# CW308_Power.net
KiCad netlist of a schematic drawn in Altium Designer
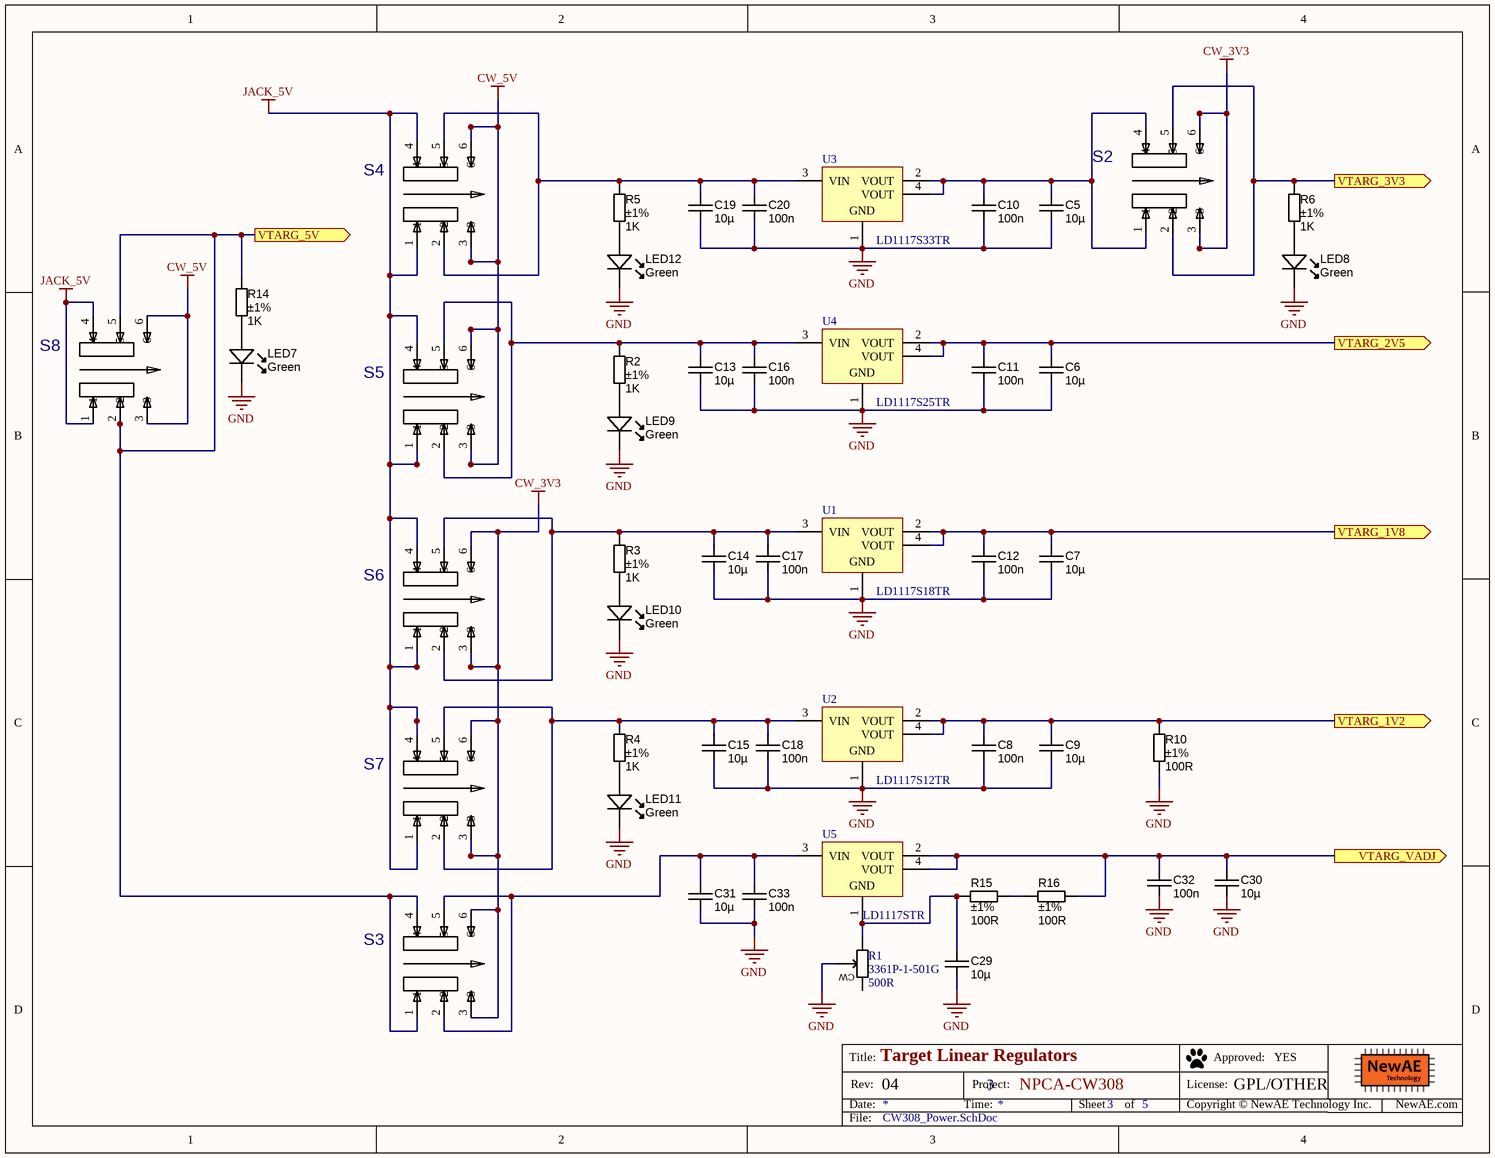
[diagram p0: CW308_Power.SchDoc]

(export (version "E")
  (design (tool "Eeschema 10.0.6"))
  (components
    (comp (ref "C5")
      (value "10µ")
      (footprint "CAPC2012X135N")
      (description "Capacitor SMD Cer 10uF 10% 10V X5R 0805")
      (fields (field (name "TOLERANCE") "±10%") (field (name "Comment") "approved sub OK"))
      (libsource (lib "PBL - Capacitors") (part "CAPC_10u_0805_10V"))
    )
    (comp (ref "C6")
      (value "10µ")
      (footprint "CAPC2012X135N")
      (description "Capacitor SMD Cer 10uF 10% 10V X5R 0805")
      (fields (field (name "TOLERANCE") "±10%") (field (name "Comment") "approved sub OK"))
      (libsource (lib "PBL - Capacitors") (part "CAPC_10u_0805_10V"))
    )
    (comp (ref "C7")
      (value "10µ")
      (footprint "CAPC2012X135N")
      (description "Capacitor SMD Cer 10uF 10% 10V X5R 0805")
      (fields (field (name "TOLERANCE") "±10%") (field (name "Comment") "approved sub OK"))
      (libsource (lib "PBL - Capacitors") (part "CAPC_10u_0805_10V"))
    )
    (comp (ref "C8")
      (value "100n")
      (footprint "CAPC1608X90N")
      (description "Capacitor SMD Cer 100nF 10% 50V X7R 0603")
      (fields (field (name "TOLERANCE") "±10%") (field (name "Comment") "approved sub OK"))
      (libsource (lib "PBL - Capacitors") (part "CAPC_100n_0603_X7R_50V_10%"))
    )
    (comp (ref "C9")
      (value "10µ")
      (footprint "CAPC2012X135N")
      (description "Capacitor SMD Cer 10uF 10% 10V X5R 0805")
      (fields (field (name "TOLERANCE") "±10%") (field (name "Comment") "approved sub OK"))
      (libsource (lib "PBL - Capacitors") (part "CAPC_10u_0805_10V"))
    )
    (comp (ref "C10")
      (value "100n")
      (footprint "CAPC1608X90N")
      (description "Capacitor SMD Cer 100nF 10% 50V X7R 0603")
      (fields (field (name "TOLERANCE") "±10%") (field (name "Comment") "approved sub OK"))
      (libsource (lib "PBL - Capacitors") (part "CAPC_100n_0603_X7R_50V_10%"))
    )
    (comp (ref "C11")
      (value "100n")
      (footprint "CAPC1608X90N")
      (description "Capacitor SMD Cer 100nF 10% 50V X7R 0603")
      (fields (field (name "TOLERANCE") "±10%") (field (name "Comment") "approved sub OK"))
      (libsource (lib "PBL - Capacitors") (part "CAPC_100n_0603_X7R_50V_10%"))
    )
    (comp (ref "C12")
      (value "100n")
      (footprint "CAPC1608X90N")
      (description "Capacitor SMD Cer 100nF 10% 50V X7R 0603")
      (fields (field (name "TOLERANCE") "±10%") (field (name "Comment") "approved sub OK"))
      (libsource (lib "PBL - Capacitors") (part "CAPC_100n_0603_X7R_50V_10%"))
    )
    (comp (ref "C13")
      (value "10µ")
      (footprint "CAPC2012X135N")
      (description "Capacitor SMD Cer 10uF 10% 10V X5R 0805")
      (fields (field (name "TOLERANCE") "±10%") (field (name "Comment") "approved sub OK"))
      (libsource (lib "PBL - Capacitors") (part "CAPC_10u_0805_10V"))
    )
    (comp (ref "C14")
      (value "10µ")
      (footprint "CAPC2012X135N")
      (description "Capacitor SMD Cer 10uF 10% 10V X5R 0805")
      (fields (field (name "TOLERANCE") "±10%") (field (name "Comment") "approved sub OK"))
      (libsource (lib "PBL - Capacitors") (part "CAPC_10u_0805_10V"))
    )
    (comp (ref "C15")
      (value "10µ")
      (footprint "CAPC2012X135N")
      (description "Capacitor SMD Cer 10uF 10% 10V X5R 0805")
      (fields (field (name "TOLERANCE") "±10%") (field (name "Comment") "approved sub OK"))
      (libsource (lib "PBL - Capacitors") (part "CAPC_10u_0805_10V"))
    )
    (comp (ref "C16")
      (value "100n")
      (footprint "CAPC1608X90N")
      (description "Capacitor SMD Cer 100nF 10% 50V X7R 0603")
      (fields (field (name "TOLERANCE") "±10%") (field (name "Comment") "approved sub OK"))
      (libsource (lib "PBL - Capacitors") (part "CAPC_100n_0603_X7R_50V_10%"))
    )
    (comp (ref "C17")
      (value "100n")
      (footprint "CAPC1608X90N")
      (description "Capacitor SMD Cer 100nF 10% 50V X7R 0603")
      (fields (field (name "TOLERANCE") "±10%") (field (name "Comment") "approved sub OK"))
      (libsource (lib "PBL - Capacitors") (part "CAPC_100n_0603_X7R_50V_10%"))
    )
    (comp (ref "C18")
      (value "100n")
      (footprint "CAPC1608X90N")
      (description "Capacitor SMD Cer 100nF 10% 50V X7R 0603")
      (fields (field (name "TOLERANCE") "±10%") (field (name "Comment") "approved sub OK"))
      (libsource (lib "PBL - Capacitors") (part "CAPC_100n_0603_X7R_50V_10%"))
    )
    (comp (ref "C19")
      (value "10µ")
      (footprint "CAPC2012X135N")
      (description "Capacitor SMD Cer 10uF 10% 10V X5R 0805")
      (fields (field (name "TOLERANCE") "±10%") (field (name "Comment") "approved sub OK"))
      (libsource (lib "PBL - Capacitors") (part "CAPC_10u_0805_10V"))
    )
    (comp (ref "C20")
      (value "100n")
      (footprint "CAPC1608X90N")
      (description "Capacitor SMD Cer 100nF 10% 50V X7R 0603")
      (fields (field (name "TOLERANCE") "±10%") (field (name "Comment") "approved sub OK"))
      (libsource (lib "PBL - Capacitors") (part "CAPC_100n_0603_X7R_50V_10%"))
    )
    (comp (ref "C29")
      (value "10µ")
      (footprint "CAPC2012X135N")
      (description "Capacitor SMD Cer 10uF 10% 10V X5R 0805")
      (fields (field (name "TOLERANCE") "±10%") (field (name "Comment") "approved sub OK"))
      (libsource (lib "PBL - Capacitors") (part "CAPC_10u_0805_10V"))
    )
    (comp (ref "C30")
      (value "10µ")
      (footprint "CAPC2012X135N")
      (description "Capacitor SMD Cer 10uF 10% 10V X5R 0805")
      (fields (field (name "TOLERANCE") "±10%") (field (name "Comment") "approved sub OK"))
      (libsource (lib "PBL - Capacitors") (part "CAPC_10u_0805_10V"))
    )
    (comp (ref "C31")
      (value "10µ")
      (footprint "CAPC2012X135N")
      (description "Capacitor SMD Cer 10uF 10% 10V X5R 0805")
      (fields (field (name "TOLERANCE") "±10%") (field (name "Comment") "approved sub OK"))
      (libsource (lib "PBL - Capacitors") (part "CAPC_10u_0805_10V"))
    )
    (comp (ref "C32")
      (value "100n")
      (footprint "CAPC1608X90N")
      (description "Capacitor SMD Cer 100nF 10% 50V X7R 0603")
      (fields (field (name "TOLERANCE") "±10%") (field (name "Comment") "approved sub OK"))
      (libsource (lib "PBL - Capacitors") (part "CAPC_100n_0603_X7R_50V_10%"))
    )
    (comp (ref "C33")
      (value "100n")
      (footprint "CAPC1608X90N")
      (description "Capacitor SMD Cer 100nF 10% 50V X7R 0603")
      (fields (field (name "TOLERANCE") "±10%") (field (name "Comment") "approved sub OK"))
      (libsource (lib "PBL - Capacitors") (part "CAPC_100n_0603_X7R_50V_10%"))
    )
    (comp (ref "LED7")
      (value "Green")
      (footprint "LED-0603-GREEN")
      (description "LED 0603 SMD Green 570nm 50mcd 20mA")
      (libsource (lib "PBL - Light Sources") (part "LED_SMD_Green_0603_570nm"))
    )
    (comp (ref "LED8")
      (value "Green")
      (footprint "LED-0603-GREEN")
      (description "LED 0603 SMD Green 570nm 50mcd 20mA")
      (libsource (lib "PBL - Light Sources") (part "LED_SMD_Green_0603_570nm"))
    )
    (comp (ref "LED9")
      (value "Green")
      (footprint "LED-0603-GREEN")
      (description "LED 0603 SMD Green 570nm 50mcd 20mA")
      (libsource (lib "PBL - Light Sources") (part "LED_SMD_Green_0603_570nm"))
    )
    (comp (ref "LED10")
      (value "Green")
      (footprint "LED-0603-GREEN")
      (description "LED 0603 SMD Green 570nm 50mcd 20mA")
      (libsource (lib "PBL - Light Sources") (part "LED_SMD_Green_0603_570nm"))
    )
    (comp (ref "LED11")
      (value "Green")
      (footprint "LED-0603-GREEN")
      (description "LED 0603 SMD Green 570nm 50mcd 20mA")
      (libsource (lib "PBL - Light Sources") (part "LED_SMD_Green_0603_570nm"))
    )
    (comp (ref "LED12")
      (value "Green")
      (footprint "LED-0603-GREEN")
      (description "LED 0603 SMD Green 570nm 50mcd 20mA")
      (libsource (lib "PBL - Light Sources") (part "LED_SMD_Green_0603_570nm"))
    )
    (comp (ref "R1")
      (value "3361P-1-501G")
      (footprint "NewAE_AltiumLib:BOURNS-3361P")
      (description "500 ohm, single-turn trimmer")
      (fields (field (name "ALTIUM_VALUE") "500R"))
      (libsource (lib "NewAE_AltiumLib") (part "3361P-1-501G"))
    )
    (comp (ref "R2")
      (value "1K")
      (footprint "RESC1608X55N")
      (description "Resistor SMD chip 1k Ohm 0.1W 1% 0603")
      (fields (field (name "TOLERANCE") "±1%") (field (name "Comment") "Thick Film"))
      (libsource (lib "PBL - Resistors") (part "RES_1K_0603_1%"))
    )
    (comp (ref "R3")
      (value "1K")
      (footprint "RESC1608X55N")
      (description "Resistor SMD chip 1k Ohm 0.1W 1% 0603")
      (fields (field (name "TOLERANCE") "±1%") (field (name "Comment") "Thick Film"))
      (libsource (lib "PBL - Resistors") (part "RES_1K_0603_1%"))
    )
    (comp (ref "R4")
      (value "1K")
      (footprint "RESC1608X55N")
      (description "Resistor SMD chip 1k Ohm 0.1W 1% 0603")
      (fields (field (name "TOLERANCE") "±1%") (field (name "Comment") "Thick Film"))
      (libsource (lib "PBL - Resistors") (part "RES_1K_0603_1%"))
    )
    (comp (ref "R5")
      (value "1K")
      (footprint "RESC1608X55N")
      (description "Resistor SMD chip 1k Ohm 0.1W 1% 0603")
      (fields (field (name "TOLERANCE") "±1%") (field (name "Comment") "Thick Film"))
      (libsource (lib "PBL - Resistors") (part "RES_1K_0603_1%"))
    )
    (comp (ref "R6")
      (value "1K")
      (footprint "RESC1608X55N")
      (description "Resistor SMD chip 1k Ohm 0.1W 1% 0603")
      (fields (field (name "TOLERANCE") "±1%") (field (name "Comment") "Thick Film"))
      (libsource (lib "PBL - Resistors") (part "RES_1K_0603_1%"))
    )
    (comp (ref "R10")
      (value "100R")
      (footprint "RESC1608X55N")
      (description "Resistor SMD chip 100 Ohm 0.1W 1% 0603")
      (fields (field (name "TOLERANCE") "±1%") (field (name "Comment") "Thick Film"))
      (libsource (lib "PBL - Resistors") (part "RES_100R_0603_1%"))
    )
    (comp (ref "R14")
      (value "1K")
      (footprint "RESC1608X55N")
      (description "Resistor SMD chip 1k Ohm 0.1W 1% 0603")
      (fields (field (name "TOLERANCE") "±1%") (field (name "Comment") "Thick Film"))
      (libsource (lib "PBL - Resistors") (part "RES_1K_0603_1%"))
    )
    (comp (ref "R15")
      (value "100R")
      (footprint "RESC1608X55N")
      (description "Resistor SMD chip 100 Ohm 0.1W 1% 0603")
      (fields (field (name "TOLERANCE") "±1%") (field (name "Comment") "Thick Film"))
      (libsource (lib "") (part "RES_100R_0603_1%_1"))
    )
    (comp (ref "R16")
      (value "100R")
      (footprint "RESC1608X55N")
      (description "Resistor SMD chip 100 Ohm 0.1W 1% 0603")
      (fields (field (name "TOLERANCE") "±1%") (field (name "Comment") "Thick Film"))
      (libsource (lib "") (part "RES_100R_0603_1%_1"))
    )
    (comp (ref "S2")
      (value "JS202011SCQN")
      (footprint "SW_JS202011SCQN")
      (description "DPDT SMD Switch, 300mA")
      (libsource (lib "") (part "JS202011SCQN_2"))
    )
    (comp (ref "S3")
      (value "JS202011SCQN")
      (footprint "SW_JS202011SCQN")
      (description "DPDT SMD Switch, 300mA")
      (libsource (lib "NewAE_AltiumLib") (part "JS202011SCQN"))
    )
    (comp (ref "S4")
      (value "JS202011SCQN")
      (footprint "SW_JS202011SCQN")
      (description "DPDT SMD Switch, 300mA")
      (libsource (lib "NewAE_AltiumLib") (part "JS202011SCQN"))
    )
    (comp (ref "S5")
      (value "JS202011SCQN")
      (footprint "SW_JS202011SCQN")
      (description "DPDT SMD Switch, 300mA")
      (libsource (lib "NewAE_AltiumLib") (part "JS202011SCQN"))
    )
    (comp (ref "S6")
      (value "JS202011SCQN")
      (footprint "SW_JS202011SCQN")
      (description "DPDT SMD Switch, 300mA")
      (libsource (lib "") (part "JS202011SCQN_1"))
    )
    (comp (ref "S7")
      (value "JS202011SCQN")
      (footprint "SW_JS202011SCQN")
      (description "DPDT SMD Switch, 300mA")
      (libsource (lib "NewAE_AltiumLib") (part "JS202011SCQN"))
    )
    (comp (ref "S8")
      (value "JS202011SCQN")
      (footprint "SW_JS202011SCQN")
      (description "DPDT SMD Switch, 300mA")
      (libsource (lib "NewAE_AltiumLib") (part "JS202011SCQN"))
    )
    (comp (ref "U1")
      (value "LD1117S18TR")
      (footprint "SOT-223_M")
      (description "Fixed Low Drop Positive Voltage Regulator, 1.8V, 4-Pin SOT-223, Tape and Reel")
      (libsource (lib "Altium Content Vault") (part "CMP-0244-00308-1"))
    )
    (comp (ref "U2")
      (value "LD1117S12TR")
      (footprint "SOT-223_M")
      (description "Fixed Low Drop Positive Voltage Regulator, 1.2V, 4-Pin SOT-223, Tape and Reel")
      (libsource (lib "Altium Content Vault") (part "PM-REG-LD1117-SOT4"))
    )
    (comp (ref "U3")
      (value "LD1117S33TR")
      (footprint "SOT-223_L")
      (description "Fixed Low Drop Positive Voltage Regulator, 3.3V, 4-Pin SOT-223, Tape and Reel")
      (libsource (lib "Altium Content Vault") (part "CMP-0244-00310-1"))
    )
    (comp (ref "U4")
      (value "LD1117S25TR")
      (footprint "SOT-223_L")
      (description "Fixed Low Drop Positive Voltage Regulator, 4-Pin SOT-223, Tape and Reel")
      (libsource (lib "Altium Content Vault") (part "PM-REG-LD1117-SOT4"))
    )
    (comp (ref "U5")
      (value "LD1117STR")
      (footprint "SOT-223_L")
      (description "Adjustable Low Drop Voltage Regulator, 1.25 to 15V, 4-Pin SOT-223, Tape and Reel")
      (libsource (lib "Altium Content Vault") (part "CMP-0244-00313-1"))
    )
  )
  (nets
    (net (code "1") (name "/VTARG_1V2") (class "Default")
      (node (ref "C8") (pin "1") (pintype "passive"))
      (node (ref "C9") (pin "1") (pintype "passive"))
      (node (ref "R10") (pin "2") (pinfunction "2_2") (pintype "passive"))
      (node (ref "U2") (pin "2") (pinfunction "VOUT_2") (pintype "power_in"))
      (node (ref "U2") (pin "4") (pinfunction "VOUT_4") (pintype "power_in"))
    )
    (net (code "2") (name "/VTARG_1V8") (class "Default")
      (node (ref "C12") (pin "1") (pintype "passive"))
      (node (ref "C7") (pin "1") (pintype "passive"))
      (node (ref "U1") (pin "2") (pinfunction "VOUT_2") (pintype "power_in"))
      (node (ref "U1") (pin "4") (pinfunction "VOUT_4") (pintype "power_in"))
    )
    (net (code "3") (name "/VTARG_2V5") (class "Default")
      (node (ref "C11") (pin "1") (pintype "passive"))
      (node (ref "C6") (pin "1") (pintype "passive"))
      (node (ref "U4") (pin "2") (pinfunction "VOUT_2") (pintype "power_in"))
      (node (ref "U4") (pin "4") (pinfunction "VOUT_4") (pintype "power_in"))
    )
    (net (code "4") (name "/VTARG_3V3") (class "Default")
      (node (ref "R6") (pin "2") (pinfunction "2_2") (pintype "passive"))
      (node (ref "S2") (pin "2") (pinfunction "2_2") (pintype "passive"))
      (node (ref "S2") (pin "5") (pinfunction "5_5") (pintype "passive"))
    )
    (net (code "5") (name "/VTARG_5V") (class "Default")
      (node (ref "R14") (pin "2") (pinfunction "2_2") (pintype "passive"))
      (node (ref "S3") (pin "1") (pinfunction "1_1") (pintype "passive"))
      (node (ref "S3") (pin "4") (pinfunction "4_4") (pintype "passive"))
      (node (ref "S8") (pin "2") (pinfunction "2_2") (pintype "passive"))
      (node (ref "S8") (pin "5") (pinfunction "5_5") (pintype "passive"))
    )
    (net (code "6") (name "/VTARG_VADJ") (class "Default")
      (node (ref "C30") (pin "1") (pintype "passive"))
      (node (ref "C32") (pin "1") (pintype "passive"))
      (node (ref "R16") (pin "1") (pinfunction "1_1") (pintype "passive"))
      (node (ref "U5") (pin "2") (pinfunction "VOUT_2") (pintype "power_in"))
      (node (ref "U5") (pin "4") (pinfunction "VOUT_4") (pintype "power_in"))
    )
    (net (code "7") (name "CW_3V3") (class "Default")
      (node (ref "S2") (pin "3") (pinfunction "3_3") (pintype "passive"))
      (node (ref "S2") (pin "6") (pinfunction "6_6") (pintype "passive"))
      (node (ref "S3") (pin "3") (pinfunction "3_3") (pintype "passive"))
      (node (ref "S3") (pin "6") (pinfunction "6_6") (pintype "passive"))
      (node (ref "S6") (pin "3") (pinfunction "3_3") (pintype "passive"))
      (node (ref "S6") (pin "6") (pinfunction "6_6") (pintype "passive"))
      (node (ref "S7") (pin "3") (pinfunction "3_3") (pintype "passive"))
      (node (ref "S7") (pin "6") (pinfunction "6_6") (pintype "passive"))
    )
    (net (code "8") (name "CW_5V") (class "Default")
      (node (ref "S4") (pin "3") (pinfunction "3_3") (pintype "passive"))
      (node (ref "S4") (pin "6") (pinfunction "6_6") (pintype "passive"))
      (node (ref "S5") (pin "3") (pinfunction "3_3") (pintype "passive"))
      (node (ref "S5") (pin "6") (pinfunction "6_6") (pintype "passive"))
      (node (ref "S8") (pin "3") (pinfunction "3_3") (pintype "passive"))
      (node (ref "S8") (pin "6") (pinfunction "6_6") (pintype "passive"))
    )
    (net (code "9") (name "GND") (class "Default")
      (node (ref "C10") (pin "2") (pintype "passive"))
      (node (ref "C11") (pin "2") (pintype "passive"))
      (node (ref "C12") (pin "2") (pintype "passive"))
      (node (ref "C13") (pin "2") (pintype "passive"))
      (node (ref "C14") (pin "2") (pintype "passive"))
      (node (ref "C15") (pin "2") (pintype "passive"))
      (node (ref "C16") (pin "2") (pintype "passive"))
      (node (ref "C17") (pin "2") (pintype "passive"))
      (node (ref "C18") (pin "2") (pintype "passive"))
      (node (ref "C19") (pin "2") (pintype "passive"))
      (node (ref "C20") (pin "2") (pintype "passive"))
      (node (ref "C29") (pin "2") (pintype "passive"))
      (node (ref "C30") (pin "2") (pintype "passive"))
      (node (ref "C31") (pin "2") (pintype "passive"))
      (node (ref "C32") (pin "2") (pintype "passive"))
      (node (ref "C33") (pin "2") (pintype "passive"))
      (node (ref "C5") (pin "2") (pintype "passive"))
      (node (ref "C6") (pin "2") (pintype "passive"))
      (node (ref "C7") (pin "2") (pintype "passive"))
      (node (ref "C8") (pin "2") (pintype "passive"))
      (node (ref "C9") (pin "2") (pintype "passive"))
      (node (ref "LED10") (pin "K") (pinfunction "K_K") (pintype "passive"))
      (node (ref "LED11") (pin "K") (pinfunction "K_K") (pintype "passive"))
      (node (ref "LED12") (pin "K") (pinfunction "K_K") (pintype "passive"))
      (node (ref "LED7") (pin "K") (pinfunction "K_K") (pintype "passive"))
      (node (ref "LED8") (pin "K") (pinfunction "K_K") (pintype "passive"))
      (node (ref "LED9") (pin "K") (pinfunction "K_K") (pintype "passive"))
      (node (ref "R1") (pin "W") (pinfunction "2_W") (pintype "passive"))
      (node (ref "R10") (pin "1") (pinfunction "1_1") (pintype "passive"))
      (node (ref "U1") (pin "1") (pinfunction "GND_1") (pintype "power_in"))
      (node (ref "U2") (pin "1") (pinfunction "GND_1") (pintype "power_in"))
      (node (ref "U3") (pin "1") (pinfunction "GND_1") (pintype "power_in"))
      (node (ref "U4") (pin "1") (pinfunction "GND_1") (pintype "power_in"))
    )
    (net (code "10") (name "JACK_5V") (class "Default")
      (node (ref "S4") (pin "1") (pinfunction "1_1") (pintype "passive"))
      (node (ref "S4") (pin "4") (pinfunction "4_4") (pintype "passive"))
      (node (ref "S5") (pin "1") (pinfunction "1_1") (pintype "passive"))
      (node (ref "S5") (pin "4") (pinfunction "4_4") (pintype "passive"))
      (node (ref "S6") (pin "1") (pinfunction "1_1") (pintype "passive"))
      (node (ref "S6") (pin "4") (pinfunction "4_4") (pintype "passive"))
      (node (ref "S7") (pin "1") (pinfunction "1_1") (pintype "passive"))
      (node (ref "S7") (pin "4") (pinfunction "4_4") (pintype "passive"))
      (node (ref "S8") (pin "1") (pinfunction "1_1") (pintype "passive"))
      (node (ref "S8") (pin "4") (pinfunction "4_4") (pintype "passive"))
    )
    (net (code "11") (name "Net-(C10-Pad1)") (class "Default")
      (node (ref "C10") (pin "1") (pintype "passive"))
      (node (ref "C5") (pin "1") (pintype "passive"))
      (node (ref "S2") (pin "1") (pinfunction "1_1") (pintype "passive"))
      (node (ref "S2") (pin "4") (pinfunction "4_4") (pintype "passive"))
      (node (ref "U3") (pin "2") (pinfunction "VOUT_2") (pintype "power_in"))
      (node (ref "U3") (pin "4") (pinfunction "VOUT_4") (pintype "power_in"))
    )
    (net (code "12") (name "Net-(LED7-PadA)") (class "Default")
      (node (ref "LED7") (pin "A") (pinfunction "A_A") (pintype "passive"))
      (node (ref "R14") (pin "1") (pinfunction "1_1") (pintype "passive"))
    )
    (net (code "13") (name "Net-(LED8-PadA)") (class "Default")
      (node (ref "LED8") (pin "A") (pinfunction "A_A") (pintype "passive"))
      (node (ref "R6") (pin "1") (pinfunction "1_1") (pintype "passive"))
    )
    (net (code "14") (name "Net-(LED9-PadA)") (class "Default")
      (node (ref "LED9") (pin "A") (pinfunction "A_A") (pintype "passive"))
      (node (ref "R2") (pin "1") (pinfunction "1_1") (pintype "passive"))
    )
    (net (code "15") (name "Net-(LED10-PadA)") (class "Default")
      (node (ref "LED10") (pin "A") (pinfunction "A_A") (pintype "passive"))
      (node (ref "R3") (pin "1") (pinfunction "1_1") (pintype "passive"))
    )
    (net (code "16") (name "Net-(LED11-PadA)") (class "Default")
      (node (ref "LED11") (pin "A") (pinfunction "A_A") (pintype "passive"))
      (node (ref "R4") (pin "1") (pinfunction "1_1") (pintype "passive"))
    )
    (net (code "17") (name "Net-(LED12-PadA)") (class "Default")
      (node (ref "LED12") (pin "A") (pinfunction "A_A") (pintype "passive"))
      (node (ref "R5") (pin "1") (pinfunction "1_1") (pintype "passive"))
    )
    (net (code "18") (name "Net-(R1-1)") (class "Default")
      (node (ref "C29") (pin "1") (pintype "passive"))
      (node (ref "R1") (pin "CCW") (pinfunction "1_CCW") (pintype "passive"))
      (node (ref "R15") (pin "2") (pinfunction "2_2") (pintype "passive"))
      (node (ref "U5") (pin "1") (pinfunction "GND_1") (pintype "power_in"))
    )
    (net (code "19") (name "Net-(R15-Pad1)") (class "Default")
      (node (ref "R15") (pin "1") (pinfunction "1_1") (pintype "passive"))
      (node (ref "R16") (pin "2") (pinfunction "2_2") (pintype "passive"))
    )
    (net (code "20") (name "Net-(U1-VIN)") (class "Default")
      (node (ref "C14") (pin "1") (pintype "passive"))
      (node (ref "C17") (pin "1") (pintype "passive"))
      (node (ref "R3") (pin "2") (pinfunction "2_2") (pintype "passive"))
      (node (ref "S6") (pin "2") (pinfunction "2_2") (pintype "passive"))
      (node (ref "S6") (pin "5") (pinfunction "5_5") (pintype "passive"))
      (node (ref "U1") (pin "3") (pinfunction "VIN_3") (pintype "power_in"))
    )
    (net (code "21") (name "Net-(U2-VIN)") (class "Default")
      (node (ref "C15") (pin "1") (pintype "passive"))
      (node (ref "C18") (pin "1") (pintype "passive"))
      (node (ref "R4") (pin "2") (pinfunction "2_2") (pintype "passive"))
      (node (ref "S7") (pin "2") (pinfunction "2_2") (pintype "passive"))
      (node (ref "S7") (pin "5") (pinfunction "5_5") (pintype "passive"))
      (node (ref "U2") (pin "3") (pinfunction "VIN_3") (pintype "power_in"))
    )
    (net (code "22") (name "Net-(U3-VIN)") (class "Default")
      (node (ref "C19") (pin "1") (pintype "passive"))
      (node (ref "C20") (pin "1") (pintype "passive"))
      (node (ref "R5") (pin "2") (pinfunction "2_2") (pintype "passive"))
      (node (ref "S4") (pin "2") (pinfunction "2_2") (pintype "passive"))
      (node (ref "S4") (pin "5") (pinfunction "5_5") (pintype "passive"))
      (node (ref "U3") (pin "3") (pinfunction "VIN_3") (pintype "power_in"))
    )
    (net (code "23") (name "Net-(U4-VIN)") (class "Default")
      (node (ref "C13") (pin "1") (pintype "passive"))
      (node (ref "C16") (pin "1") (pintype "passive"))
      (node (ref "R2") (pin "2") (pinfunction "2_2") (pintype "passive"))
      (node (ref "S5") (pin "2") (pinfunction "2_2") (pintype "passive"))
      (node (ref "S5") (pin "5") (pinfunction "5_5") (pintype "passive"))
      (node (ref "U4") (pin "3") (pinfunction "VIN_3") (pintype "power_in"))
    )
    (net (code "24") (name "Net-(U5-VIN)") (class "Default")
      (node (ref "C31") (pin "1") (pintype "passive"))
      (node (ref "C33") (pin "1") (pintype "passive"))
      (node (ref "S3") (pin "2") (pinfunction "2_2") (pintype "passive"))
      (node (ref "S3") (pin "5") (pinfunction "5_5") (pintype "passive"))
      (node (ref "U5") (pin "3") (pinfunction "VIN_3") (pintype "power_in"))
    )
    (net (code "25") (name "unconnected-(R1-3-PadCW)") (class "Default")
      (node (ref "R1") (pin "CW") (pinfunction "3_CW") (pintype "passive"))
    )
  )
)
